# MCU.net
KiCad netlist of a schematic drawn in Altium Designer
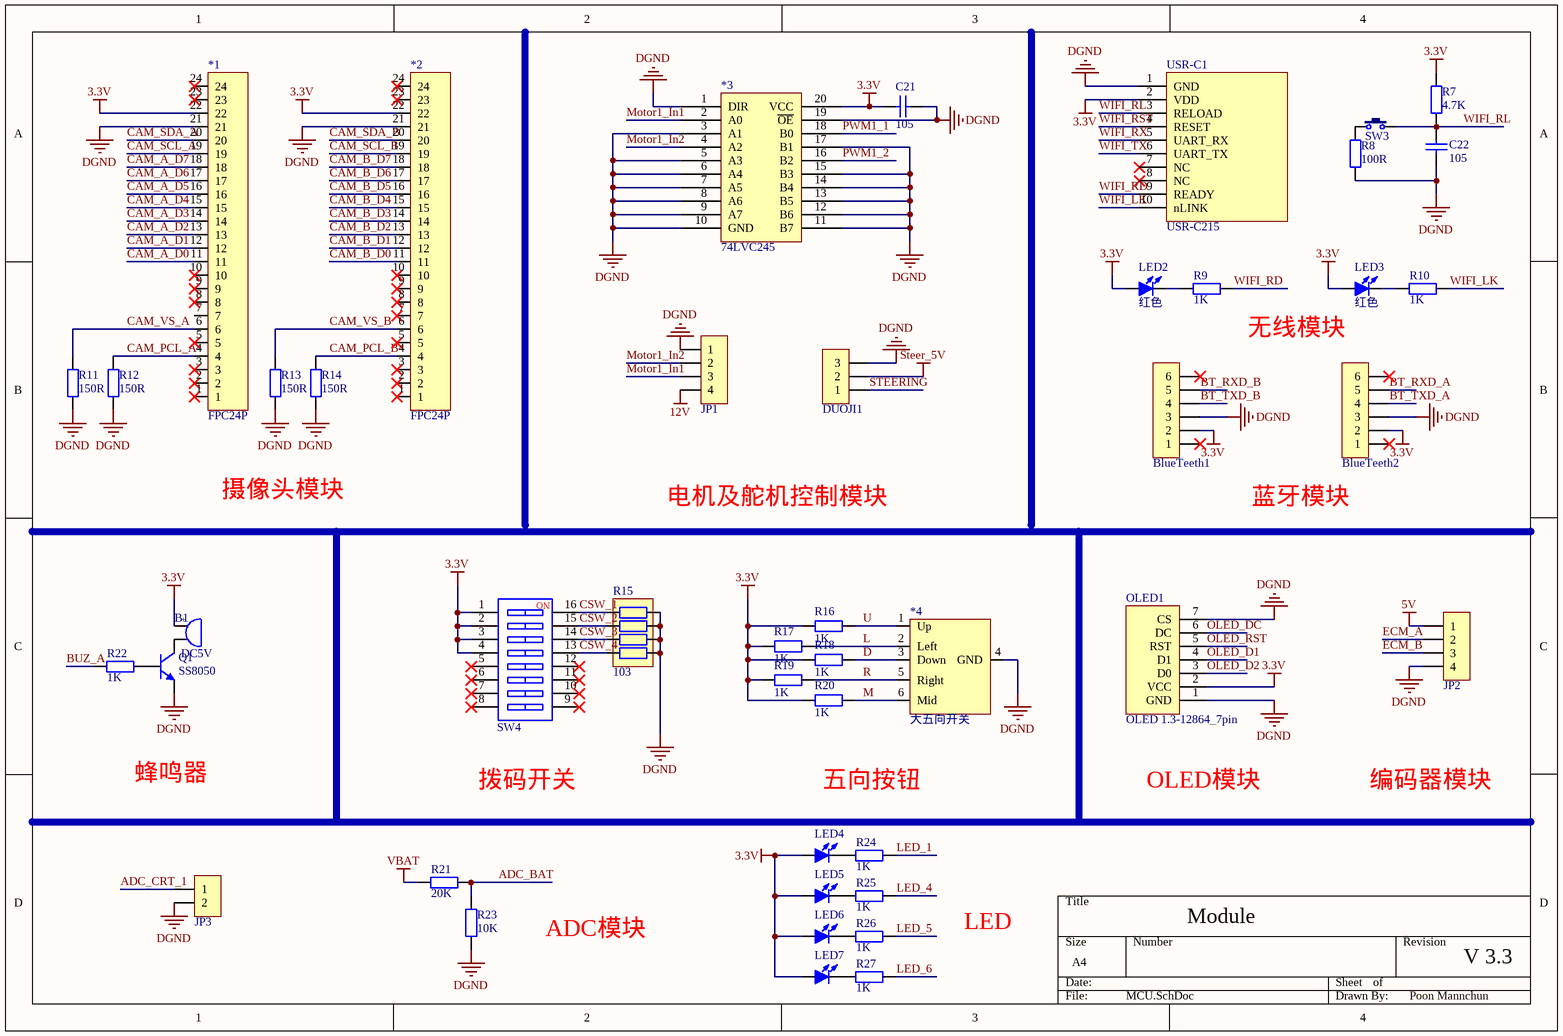
[diagram p0: MCU.SchDoc]

(export (version "E")
  (design (tool "Eeschema 10.0.6"))
  (components
    (comp (ref "*1")
      (value "FPC24P")
      (footprint "FH12-24S-0.5SV")
      (libsource (lib "LongMen") (part "FPC24P"))
    )
    (comp (ref "*2")
      (value "FPC24P")
      (footprint "FH12-24S-0.5SV")
      (libsource (lib "LongMen") (part "FPC24P"))
    )
    (comp (ref "*3") (value "74LVC245") (footprint "TSSOP-20") (libsource (lib "MIC5219") (part "74LVC245")))
    (comp (ref "*4") (value "大五向开关") (footprint "五向") (libsource (lib "5.1   - 按键-开关") (part "大五向开关")))
    (comp (ref "B1")
      (value "DC5V")
      (footprint "BEEP 5x9x5.5")
      (description "蜂鸣器")
      (fields (field (name "版权归属") "源创客"))
      (libsource (lib "未分类器件") (part "BEEP"))
    )
    (comp (ref "BlueTeeth1")
      (value "HDR-1X6")
      (footprint "HDR2.54-LI-6P")
      (description "6P接插件")
      (fields (field (name "版权归属") "源创客"))
      (libsource (lib "接插件") (part "Header 6"))
    )
    (comp (ref "BlueTeeth2")
      (value "HDR-1X6")
      (footprint "HDR2.54-LI-6P")
      (description "6P接插件")
      (fields (field (name "版权归属") "源创客"))
      (libsource (lib "接插件") (part "Header 6"))
    )
    (comp (ref "C21")
      (value "105")
      (footprint "C 0805_L")
      (description "Capacitor")
      (fields (field (name "PUBLISHER") "Altium Limited"))
      (libsource (lib "6-MK60DN512VLL10核心板") (part "CAP"))
    )
    (comp (ref "C22")
      (value "105")
      (footprint "C 0805_L")
      (description "Capacitor")
      (fields (field (name "PUBLISHER") "Altium Limited"))
      (libsource (lib "6-MK60DN512VLL10核心板") (part "CAP"))
    )
    (comp (ref "DUOJI1")
      (value "HDR-1X3")
      (footprint "HDR2.54-LI-3P")
      (description "3P接插件")
      (fields (field (name "版权归属") "源创客"))
      (libsource (lib "接插件") (part "Header 3"))
    )
    (comp (ref "JP1")
      (value "HDR-1X4")
      (footprint "HDR2.54-LI-4P")
      (description "4P接插件")
      (fields (field (name "版权归属") "源创客"))
      (libsource (lib "4.5   - 接插件-脚距2.54") (part "Header 4"))
    )
    (comp (ref "JP2")
      (value "HDR-1X4")
      (footprint "HDR2.54-LI-4P")
      (description "4P接插件")
      (fields (field (name "版权归属") "源创客"))
      (libsource (lib "4.5   - 接插件-脚距2.54") (part "Header 4"))
    )
    (comp (ref "JP3")
      (value "HDR-1X2")
      (footprint "HDR2.54-LI-2P")
      (description "2P接插件")
      (fields (field (name "版权归属") "源创客"))
      (libsource (lib "4.5   - 接插件-脚距2.54") (part "Header 2"))
    )
    (comp (ref "LED2")
      (value "红色")
      (footprint "LED 0805B")
      (description "贴片LED")
      (fields (field (name "版权归属") "源创客"))
      (libsource (lib "LED") (part "LED-SMD"))
    )
    (comp (ref "LED3")
      (value "红色")
      (footprint "LED 0805B")
      (description "贴片LED")
      (fields (field (name "版权归属") "源创客"))
      (libsource (lib "LED") (part "LED-SMD"))
    )
    (comp (ref "LED4")
      (value "红色")
      (footprint "LED 0805B")
      (description "贴片LED")
      (fields (field (name "版权归属") "源创客"))
      (libsource (lib "LED") (part "LED-SMD"))
    )
    (comp (ref "LED5")
      (value "红色")
      (footprint "LED 0805B")
      (description "贴片LED")
      (fields (field (name "版权归属") "源创客"))
      (libsource (lib "LED") (part "LED-SMD"))
    )
    (comp (ref "LED6")
      (value "红色")
      (footprint "LED 0805B")
      (description "贴片LED")
      (fields (field (name "版权归属") "源创客"))
      (libsource (lib "LED") (part "LED-SMD"))
    )
    (comp (ref "LED7")
      (value "红色")
      (footprint "LED 0805B")
      (description "贴片LED")
      (fields (field (name "版权归属") "源创客"))
      (libsource (lib "LED") (part "LED-SMD"))
    )
    (comp (ref "OLED1")
      (value "OLED 1.3-12864_7pin")
      (footprint "HDR2.54-M-LI-7P")
      (description "12864 点阵屏")
      (fields (field (name "版权归属") "源创客"))
      (libsource (lib "9.2   - 显示器件") (part "OLED 1.3-12864_7pin"))
    )
    (comp (ref "Q1")
      (value "SS8050")
      (footprint "SOT23-3L")
      (description "高频放大-NPN型")
      (fields (field (name "版权归属") "源创客"))
      (libsource (lib "三极管") (part "8050-SMD"))
    )
    (comp (ref "R7")
      (value "4.7K")
      (footprint "R 0805_L")
      (description "Resistor")
      (fields (field (name "PUBLISHER") "Altium Limited"))
      (libsource (lib "") (part "Res2_1"))
    )
    (comp (ref "R8")
      (value "100R")
      (footprint "R 0805_L")
      (description "Resistor")
      (fields (field (name "PUBLISHER") "Altium Limited"))
      (libsource (lib "") (part "Res2_1"))
    )
    (comp (ref "R9")
      (value "1K")
      (footprint "R 0805_L")
      (description "Resistor")
      (fields (field (name "PUBLISHER") "Altium Limited"))
      (libsource (lib "6-MK60DN512VLL10核心板") (part "Res2"))
    )
    (comp (ref "R10")
      (value "1K")
      (footprint "R 0805_L")
      (description "Resistor")
      (fields (field (name "PUBLISHER") "Altium Limited"))
      (libsource (lib "6-MK60DN512VLL10核心板") (part "Res2"))
    )
    (comp (ref "R11")
      (value "150R")
      (footprint "R 0805_L")
      (description "Resistor")
      (fields (field (name "PUBLISHER") "Altium Limited"))
      (libsource (lib "") (part "Res2_1"))
    )
    (comp (ref "R12")
      (value "150R")
      (footprint "R 0805_L")
      (description "Resistor")
      (fields (field (name "PUBLISHER") "Altium Limited"))
      (libsource (lib "") (part "Res2_1"))
    )
    (comp (ref "R13")
      (value "150R")
      (footprint "R 0805_L")
      (description "Resistor")
      (fields (field (name "PUBLISHER") "Altium Limited"))
      (libsource (lib "") (part "Res2_1"))
    )
    (comp (ref "R14")
      (value "150R")
      (footprint "R 0805_L")
      (description "Resistor")
      (fields (field (name "PUBLISHER") "Altium Limited"))
      (libsource (lib "") (part "Res2_1"))
    )
    (comp (ref "R15")
      (value "103")
      (footprint "RCA-8P4R-0603")
      (description "贴片网络排阻")
      (fields (field (name "版权归属") "源创客"))
      (libsource (lib "3.1   - 电阻-电容-电感") (part "R-8P4R"))
    )
    (comp (ref "R16")
      (value "1K")
      (footprint "R 0805_L")
      (description "贴片电阻")
      (fields (field (name "版权归属") "源创客"))
      (libsource (lib "3.1   - 电阻-电容-电感") (part "R"))
    )
    (comp (ref "R17")
      (value "1K")
      (footprint "R 0805_L")
      (description "贴片电阻")
      (fields (field (name "版权归属") "源创客"))
      (libsource (lib "3.1   - 电阻-电容-电感") (part "R"))
    )
    (comp (ref "R18")
      (value "1K")
      (footprint "R 0805_L")
      (description "贴片电阻")
      (fields (field (name "版权归属") "源创客"))
      (libsource (lib "3.1   - 电阻-电容-电感") (part "R"))
    )
    (comp (ref "R19")
      (value "1K")
      (footprint "R 0805_L")
      (description "贴片电阻")
      (fields (field (name "版权归属") "源创客"))
      (libsource (lib "3.1   - 电阻-电容-电感") (part "R"))
    )
    (comp (ref "R20")
      (value "1K")
      (footprint "R 0805_L")
      (description "贴片电阻")
      (fields (field (name "版权归属") "源创客"))
      (libsource (lib "3.1   - 电阻-电容-电感") (part "R"))
    )
    (comp (ref "R21")
      (value "20K")
      (footprint "R 0805_L")
      (description "Resistor")
      (fields (field (name "PUBLISHER") "Altium Limited"))
      (libsource (lib "6-MK60DN512VLL10核心板") (part "Res2"))
    )
    (comp (ref "R22")
      (value "1K")
      (footprint "R 0805_L")
      (description "Resistor")
      (fields (field (name "PUBLISHER") "Altium Limited"))
      (libsource (lib "6-MK60DN512VLL10核心板") (part "Res2"))
    )
    (comp (ref "R23")
      (value "10K")
      (footprint "R 0805_L")
      (description "Resistor")
      (fields (field (name "PUBLISHER") "Altium Limited"))
      (libsource (lib "") (part "Res2_1"))
    )
    (comp (ref "R24")
      (value "1K")
      (footprint "R 0805_L")
      (description "Resistor")
      (fields (field (name "PUBLISHER") "Altium Limited"))
      (libsource (lib "6-MK60DN512VLL10核心板") (part "Res2"))
    )
    (comp (ref "R25")
      (value "1K")
      (footprint "R 0805_L")
      (description "Resistor")
      (fields (field (name "PUBLISHER") "Altium Limited"))
      (libsource (lib "6-MK60DN512VLL10核心板") (part "Res2"))
    )
    (comp (ref "R26")
      (value "1K")
      (footprint "R 0805_L")
      (description "Resistor")
      (fields (field (name "PUBLISHER") "Altium Limited"))
      (libsource (lib "6-MK60DN512VLL10核心板") (part "Res2"))
    )
    (comp (ref "R27")
      (value "1K")
      (footprint "R 0805_L")
      (description "Resistor")
      (fields (field (name "PUBLISHER") "Altium Limited"))
      (libsource (lib "6-MK60DN512VLL10核心板") (part "Res2"))
    )
    (comp (ref "SW3")
      (value "3x6x5")
      (footprint "TSW SMD-3*6*2.5")
      (description "3x6轻触开关")
      (fields (field (name "版权归属") "源创客"))
      (libsource (lib "按键-开关") (part "TSW 3x6"))
    )
    (comp (ref "SW4")
      (value "CSW-8P")
      (footprint "CSW1.27 SMD-8P")
      (description "8路编码开关")
      (fields (field (name "版权归属") "源创客"))
      (libsource (lib "5.1   - 按键-开关") (part "CSW-8P"))
    )
    (comp (ref "USR-C1")
      (value "USR-C215")
      (footprint "DIP2.0*1-10-M")
      (fields (field (name "PUBLISHER") "*"))
      (libsource (lib "13.1 - 模块") (part "USR-C215"))
    )
  )
  (nets
    (net (code "1") (name "/ADC_BAT") (class "Default")
      (node (ref "R21") (pin "2") (pinfunction "2_2") (pintype "passive"))
      (node (ref "R23") (pin "2") (pinfunction "2_2") (pintype "passive"))
    )
    (net (code "2") (name "/ADC_CRT_1") (class "Default")
      (node (ref "JP3") (pin "1") (pinfunction "1_1") (pintype "passive"))
    )
    (net (code "3") (name "/BT_RXD_A") (class "Default")
      (node (ref "BlueTeeth2") (pin "5") (pinfunction "5_5") (pintype "passive"))
    )
    (net (code "4") (name "/BT_RXD_B") (class "Default")
      (node (ref "BlueTeeth1") (pin "5") (pinfunction "5_5") (pintype "passive"))
    )
    (net (code "5") (name "/BT_TXD_A") (class "Default")
      (node (ref "BlueTeeth2") (pin "4") (pinfunction "4_4") (pintype "passive"))
    )
    (net (code "6") (name "/BT_TXD_B") (class "Default")
      (node (ref "BlueTeeth1") (pin "4") (pinfunction "4_4") (pintype "passive"))
    )
    (net (code "7") (name "/BUZ_A") (class "Default")
      (node (ref "R22") (pin "1") (pinfunction "1_1") (pintype "passive"))
    )
    (net (code "8") (name "/CAM_A_D0") (class "Default")
      (node (ref "*1") (pin "11") (pinfunction "11_11") (pintype "passive"))
    )
    (net (code "9") (name "/CAM_A_D1") (class "Default")
      (node (ref "*1") (pin "12") (pinfunction "12_12") (pintype "passive"))
    )
    (net (code "10") (name "/CAM_A_D2") (class "Default")
      (node (ref "*1") (pin "13") (pinfunction "13_13") (pintype "passive"))
    )
    (net (code "11") (name "/CAM_A_D3") (class "Default")
      (node (ref "*1") (pin "14") (pinfunction "14_14") (pintype "passive"))
    )
    (net (code "12") (name "/CAM_A_D4") (class "Default")
      (node (ref "*1") (pin "15") (pinfunction "15_15") (pintype "passive"))
    )
    (net (code "13") (name "/CAM_A_D5") (class "Default")
      (node (ref "*1") (pin "16") (pinfunction "16_16") (pintype "passive"))
    )
    (net (code "14") (name "/CAM_A_D6") (class "Default")
      (node (ref "*1") (pin "17") (pinfunction "17_17") (pintype "passive"))
    )
    (net (code "15") (name "/CAM_A_D7") (class "Default")
      (node (ref "*1") (pin "18") (pinfunction "18_18") (pintype "passive"))
    )
    (net (code "16") (name "/CAM_B_D0") (class "Default")
      (node (ref "*2") (pin "11") (pinfunction "11_11") (pintype "passive"))
    )
    (net (code "17") (name "/CAM_B_D1") (class "Default")
      (node (ref "*2") (pin "12") (pinfunction "12_12") (pintype "passive"))
    )
    (net (code "18") (name "/CAM_B_D2") (class "Default")
      (node (ref "*2") (pin "13") (pinfunction "13_13") (pintype "passive"))
    )
    (net (code "19") (name "/CAM_B_D3") (class "Default")
      (node (ref "*2") (pin "14") (pinfunction "14_14") (pintype "passive"))
    )
    (net (code "20") (name "/CAM_B_D4") (class "Default")
      (node (ref "*2") (pin "15") (pinfunction "15_15") (pintype "passive"))
    )
    (net (code "21") (name "/CAM_B_D5") (class "Default")
      (node (ref "*2") (pin "16") (pinfunction "16_16") (pintype "passive"))
    )
    (net (code "22") (name "/CAM_B_D6") (class "Default")
      (node (ref "*2") (pin "17") (pinfunction "17_17") (pintype "passive"))
    )
    (net (code "23") (name "/CAM_B_D7") (class "Default")
      (node (ref "*2") (pin "18") (pinfunction "18_18") (pintype "passive"))
    )
    (net (code "24") (name "/CAM_PCL_A") (class "Default")
      (node (ref "*1") (pin "4") (pinfunction "4_4") (pintype "passive"))
      (node (ref "R12") (pin "2") (pinfunction "2_2") (pintype "passive"))
    )
    (net (code "25") (name "/CAM_PCL_B") (class "Default")
      (node (ref "*2") (pin "4") (pinfunction "4_4") (pintype "passive"))
      (node (ref "R14") (pin "2") (pinfunction "2_2") (pintype "passive"))
    )
    (net (code "26") (name "/CAM_SCL_A") (class "Default")
      (node (ref "*1") (pin "19") (pinfunction "19_19") (pintype "passive"))
    )
    (net (code "27") (name "/CAM_SCL_B") (class "Default")
      (node (ref "*2") (pin "19") (pinfunction "19_19") (pintype "passive"))
    )
    (net (code "28") (name "/CAM_SDA_A") (class "Default")
      (node (ref "*1") (pin "20") (pinfunction "20_20") (pintype "passive"))
    )
    (net (code "29") (name "/CAM_SDA_B") (class "Default")
      (node (ref "*2") (pin "20") (pinfunction "20_20") (pintype "passive"))
    )
    (net (code "30") (name "/CAM_VS_A") (class "Default")
      (node (ref "*1") (pin "6") (pinfunction "6_6") (pintype "passive"))
      (node (ref "R11") (pin "2") (pinfunction "2_2") (pintype "passive"))
    )
    (net (code "31") (name "/CAM_VS_B") (class "Default")
      (node (ref "*2") (pin "6") (pinfunction "6_6") (pintype "passive"))
      (node (ref "R13") (pin "2") (pinfunction "2_2") (pintype "passive"))
    )
    (net (code "32") (name "/CSW_1") (class "Default")
      (node (ref "R15") (pin "1") (pinfunction "1_1") (pintype "passive"))
      (node (ref "SW4") (pin "16") (pinfunction "16_16") (pintype "passive"))
    )
    (net (code "33") (name "/CSW_2") (class "Default")
      (node (ref "R15") (pin "2") (pinfunction "2_2") (pintype "passive"))
      (node (ref "SW4") (pin "15") (pinfunction "15_15") (pintype "passive"))
    )
    (net (code "34") (name "/CSW_3") (class "Default")
      (node (ref "R15") (pin "3") (pinfunction "3_3") (pintype "passive"))
      (node (ref "SW4") (pin "14") (pinfunction "14_14") (pintype "passive"))
    )
    (net (code "35") (name "/CSW_4") (class "Default")
      (node (ref "R15") (pin "4") (pinfunction "4_4") (pintype "passive"))
      (node (ref "SW4") (pin "13") (pinfunction "13_13") (pintype "passive"))
    )
    (net (code "36") (name "/D") (class "Default")
      (node (ref "*4") (pin "3") (pinfunction "Down_3") (pintype "passive"))
      (node (ref "R18") (pin "2") (pinfunction "2_2") (pintype "passive"))
    )
    (net (code "37") (name "/ECM_A") (class "Default")
      (node (ref "JP2") (pin "2") (pinfunction "2_2") (pintype "passive"))
    )
    (net (code "38") (name "/ECM_B") (class "Default")
      (node (ref "JP2") (pin "3") (pinfunction "3_3") (pintype "passive"))
    )
    (net (code "39") (name "/L") (class "Default")
      (node (ref "*4") (pin "2") (pinfunction "Left_2") (pintype "passive"))
      (node (ref "R17") (pin "2") (pinfunction "2_2") (pintype "passive"))
    )
    (net (code "40") (name "/LED_1") (class "Default")
      (node (ref "R24") (pin "2") (pinfunction "2_2") (pintype "passive"))
    )
    (net (code "41") (name "/LED_4") (class "Default")
      (node (ref "R25") (pin "2") (pinfunction "2_2") (pintype "passive"))
    )
    (net (code "42") (name "/LED_5") (class "Default")
      (node (ref "R26") (pin "2") (pinfunction "2_2") (pintype "passive"))
    )
    (net (code "43") (name "/LED_6") (class "Default")
      (node (ref "R27") (pin "2") (pinfunction "2_2") (pintype "passive"))
    )
    (net (code "44") (name "/M") (class "Default")
      (node (ref "*4") (pin "6") (pinfunction "Mid_6") (pintype "passive"))
      (node (ref "R20") (pin "2") (pinfunction "2_2") (pintype "passive"))
    )
    (net (code "45") (name "/Motor1_In1") (class "Default")
      (node (ref "*3") (pin "2") (pinfunction "A0_2") (pintype "passive"))
      (node (ref "JP1") (pin "3") (pinfunction "3_3") (pintype "passive"))
    )
    (net (code "46") (name "/Motor1_In2") (class "Default")
      (node (ref "*3") (pin "4") (pinfunction "A2_4") (pintype "passive"))
      (node (ref "JP1") (pin "2") (pinfunction "2_2") (pintype "passive"))
    )
    (net (code "47") (name "/OLED_D1") (class "Default")
      (node (ref "OLED1") (pin "4") (pinfunction "D1_4") (pintype "passive"))
    )
    (net (code "48") (name "/OLED_D2") (class "Default")
      (node (ref "OLED1") (pin "3") (pinfunction "D0_3") (pintype "passive"))
    )
    (net (code "49") (name "/OLED_DC") (class "Default")
      (node (ref "OLED1") (pin "6") (pinfunction "DC_6") (pintype "passive"))
    )
    (net (code "50") (name "/OLED_RST") (class "Default")
      (node (ref "OLED1") (pin "5") (pinfunction "RST_5") (pintype "passive"))
    )
    (net (code "51") (name "/PWM1_1") (class "Default")
      (node (ref "*3") (pin "18") (pinfunction "B0_18") (pintype "passive"))
    )
    (net (code "52") (name "/PWM1_2") (class "Default")
      (node (ref "*3") (pin "16") (pinfunction "B2_16") (pintype "passive"))
    )
    (net (code "53") (name "/R") (class "Default")
      (node (ref "*4") (pin "5") (pinfunction "Right_5") (pintype "passive"))
      (node (ref "R19") (pin "2") (pinfunction "2_2") (pintype "passive"))
    )
    (net (code "54") (name "/STEERING") (class "Default")
      (node (ref "DUOJI1") (pin "1") (pinfunction "1_1") (pintype "passive"))
    )
    (net (code "55") (name "/U") (class "Default")
      (node (ref "*4") (pin "1") (pinfunction "Up_1") (pintype "passive"))
      (node (ref "R16") (pin "2") (pinfunction "2_2") (pintype "passive"))
    )
    (net (code "56") (name "/WIFI_LK") (class "Default")
      (node (ref "R10") (pin "2") (pinfunction "2_2") (pintype "passive"))
      (node (ref "USR-C1") (pin "10") (pinfunction "nLINK_10") (pintype "passive"))
    )
    (net (code "57") (name "/WIFI_RD") (class "Default")
      (node (ref "R9") (pin "2") (pinfunction "2_2") (pintype "passive"))
      (node (ref "USR-C1") (pin "9") (pinfunction "READY_9") (pintype "passive"))
    )
    (net (code "58") (name "/WIFI_RL") (class "Default")
      (node (ref "C22") (pin "2") (pinfunction "2_2") (pintype "passive"))
      (node (ref "R7") (pin "1") (pinfunction "1_1") (pintype "passive"))
      (node (ref "SW3") (pin "2") (pinfunction "2_2") (pintype "passive"))
      (node (ref "USR-C1") (pin "3") (pinfunction "RELOAD_3") (pintype "passive"))
    )
    (net (code "59") (name "/WIFI_RST") (class "Default")
      (node (ref "USR-C1") (pin "4") (pinfunction "RESET_4") (pintype "passive"))
    )
    (net (code "60") (name "/WIFI_RX") (class "Default")
      (node (ref "USR-C1") (pin "5") (pinfunction "UART_RX_5") (pintype "passive"))
    )
    (net (code "61") (name "/WIFI_TX") (class "Default")
      (node (ref "USR-C1") (pin "6") (pinfunction "UART_TX_6") (pintype "passive"))
    )
    (net (code "62") (name "3.3V") (class "Default")
      (node (ref "*1") (pin "22") (pinfunction "22_22") (pintype "passive"))
      (node (ref "*2") (pin "22") (pinfunction "22_22") (pintype "passive"))
      (node (ref "*3") (pin "20") (pinfunction "VCC_20") (pintype "passive"))
      (node (ref "B1") (pin "1") (pinfunction "1_1") (pintype "passive"))
      (node (ref "BlueTeeth1") (pin "2") (pinfunction "2_2") (pintype "passive"))
      (node (ref "BlueTeeth2") (pin "2") (pinfunction "2_2") (pintype "passive"))
      (node (ref "C21") (pin "2") (pinfunction "2_2") (pintype "passive"))
      (node (ref "LED2") (pin "1") (pinfunction "A_1") (pintype "passive"))
      (node (ref "LED3") (pin "1") (pinfunction "A_1") (pintype "passive"))
      (node (ref "LED4") (pin "1") (pinfunction "A_1") (pintype "passive"))
      (node (ref "LED5") (pin "1") (pinfunction "A_1") (pintype "passive"))
      (node (ref "LED6") (pin "1") (pinfunction "A_1") (pintype "passive"))
      (node (ref "LED7") (pin "1") (pinfunction "A_1") (pintype "passive"))
      (node (ref "OLED1") (pin "2") (pinfunction "VCC_2") (pintype "passive"))
      (node (ref "R16") (pin "1") (pinfunction "1_1") (pintype "passive"))
      (node (ref "R17") (pin "1") (pinfunction "1_1") (pintype "passive"))
      (node (ref "R18") (pin "1") (pinfunction "1_1") (pintype "passive"))
      (node (ref "R19") (pin "1") (pinfunction "1_1") (pintype "passive"))
      (node (ref "R20") (pin "1") (pinfunction "1_1") (pintype "passive"))
      (node (ref "R7") (pin "2") (pinfunction "2_2") (pintype "passive"))
      (node (ref "SW4") (pin "1") (pinfunction "1_1") (pintype "passive"))
      (node (ref "SW4") (pin "2") (pinfunction "2_2") (pintype "passive"))
      (node (ref "SW4") (pin "3") (pinfunction "3_3") (pintype "passive"))
      (node (ref "SW4") (pin "4") (pinfunction "4_4") (pintype "passive"))
      (node (ref "USR-C1") (pin "2") (pinfunction "VDD_2") (pintype "passive"))
    )
    (net (code "63") (name "5V") (class "Default")
      (node (ref "JP2") (pin "1") (pinfunction "1_1") (pintype "passive"))
    )
    (net (code "64") (name "12V") (class "Default")
      (node (ref "JP1") (pin "4") (pinfunction "4_4") (pintype "passive"))
    )
    (net (code "65") (name "DGND") (class "Default")
      (node (ref "*1") (pin "21") (pinfunction "21_21") (pintype "passive"))
      (node (ref "*2") (pin "21") (pinfunction "21_21") (pintype "passive"))
      (node (ref "*3") (pin "1") (pinfunction "DIR_1") (pintype "passive"))
      (node (ref "*3") (pin "10") (pinfunction "GND_10") (pintype "passive"))
      (node (ref "*3") (pin "11") (pinfunction "B7_11") (pintype "passive"))
      (node (ref "*3") (pin "12") (pinfunction "B6_12") (pintype "passive"))
      (node (ref "*3") (pin "13") (pinfunction "B5_13") (pintype "passive"))
      (node (ref "*3") (pin "14") (pinfunction "B4_14") (pintype "passive"))
      (node (ref "*3") (pin "15") (pinfunction "B3_15") (pintype "passive"))
      (node (ref "*3") (pin "17") (pinfunction "B1_17") (pintype "passive"))
      (node (ref "*3") (pin "19") (pinfunction "~{OE}_19") (pintype "passive"))
      (node (ref "*3") (pin "3") (pinfunction "A1_3") (pintype "passive"))
      (node (ref "*3") (pin "5") (pinfunction "A3_5") (pintype "passive"))
      (node (ref "*3") (pin "6") (pinfunction "A4_6") (pintype "passive"))
      (node (ref "*3") (pin "7") (pinfunction "A5_7") (pintype "passive"))
      (node (ref "*3") (pin "8") (pinfunction "A6_8") (pintype "passive"))
      (node (ref "*3") (pin "9") (pinfunction "A7_9") (pintype "passive"))
      (node (ref "*4") (pin "4") (pinfunction "GND_4") (pintype "passive"))
      (node (ref "BlueTeeth1") (pin "3") (pinfunction "3_3") (pintype "passive"))
      (node (ref "BlueTeeth2") (pin "3") (pinfunction "3_3") (pintype "passive"))
      (node (ref "C21") (pin "1") (pinfunction "1_1") (pintype "passive"))
      (node (ref "C22") (pin "1") (pinfunction "1_1") (pintype "passive"))
      (node (ref "DUOJI1") (pin "3") (pinfunction "3_3") (pintype "passive"))
      (node (ref "JP1") (pin "1") (pinfunction "1_1") (pintype "passive"))
      (node (ref "JP2") (pin "4") (pinfunction "4_4") (pintype "passive"))
      (node (ref "JP3") (pin "2") (pinfunction "2_2") (pintype "passive"))
      (node (ref "OLED1") (pin "1") (pinfunction "GND_1") (pintype "passive"))
      (node (ref "OLED1") (pin "7") (pinfunction "CS_7") (pintype "passive"))
      (node (ref "Q1") (pin "2") (pinfunction "E_2") (pintype "passive"))
      (node (ref "R11") (pin "1") (pinfunction "1_1") (pintype "passive"))
      (node (ref "R12") (pin "1") (pinfunction "1_1") (pintype "passive"))
      (node (ref "R13") (pin "1") (pinfunction "1_1") (pintype "passive"))
      (node (ref "R14") (pin "1") (pinfunction "1_1") (pintype "passive"))
      (node (ref "R15") (pin "5") (pinfunction "5_5") (pintype "passive"))
      (node (ref "R15") (pin "6") (pinfunction "6_6") (pintype "passive"))
      (node (ref "R15") (pin "7") (pinfunction "7_7") (pintype "passive"))
      (node (ref "R15") (pin "8") (pinfunction "8_8") (pintype "passive"))
      (node (ref "R23") (pin "1") (pinfunction "1_1") (pintype "passive"))
      (node (ref "R8") (pin "1") (pinfunction "1_1") (pintype "passive"))
      (node (ref "USR-C1") (pin "1") (pinfunction "GND_1") (pintype "passive"))
    )
    (net (code "66") (name "Net-(LED2-K)") (class "Default")
      (node (ref "LED2") (pin "2") (pinfunction "K_2") (pintype "passive"))
      (node (ref "R9") (pin "1") (pinfunction "1_1") (pintype "passive"))
    )
    (net (code "67") (name "Net-(LED3-K)") (class "Default")
      (node (ref "LED3") (pin "2") (pinfunction "K_2") (pintype "passive"))
      (node (ref "R10") (pin "1") (pinfunction "1_1") (pintype "passive"))
    )
    (net (code "68") (name "Net-(LED4-K)") (class "Default")
      (node (ref "LED4") (pin "2") (pinfunction "K_2") (pintype "passive"))
      (node (ref "R24") (pin "1") (pinfunction "1_1") (pintype "passive"))
    )
    (net (code "69") (name "Net-(LED5-K)") (class "Default")
      (node (ref "LED5") (pin "2") (pinfunction "K_2") (pintype "passive"))
      (node (ref "R25") (pin "1") (pinfunction "1_1") (pintype "passive"))
    )
    (net (code "70") (name "Net-(LED6-K)") (class "Default")
      (node (ref "LED6") (pin "2") (pinfunction "K_2") (pintype "passive"))
      (node (ref "R26") (pin "1") (pinfunction "1_1") (pintype "passive"))
    )
    (net (code "71") (name "Net-(LED7-K)") (class "Default")
      (node (ref "LED7") (pin "2") (pinfunction "K_2") (pintype "passive"))
      (node (ref "R27") (pin "1") (pinfunction "1_1") (pintype "passive"))
    )
    (net (code "72") (name "Net-(Q1-B)") (class "Default")
      (node (ref "Q1") (pin "1") (pinfunction "B_1") (pintype "passive"))
      (node (ref "R22") (pin "2") (pinfunction "2_2") (pintype "passive"))
    )
    (net (code "73") (name "Net-(Q1-C)") (class "Default")
      (node (ref "B1") (pin "2") (pinfunction "2_2") (pintype "passive"))
      (node (ref "Q1") (pin "3") (pinfunction "C_3") (pintype "passive"))
    )
    (net (code "74") (name "Net-(R8-Pad2)") (class "Default")
      (node (ref "R8") (pin "2") (pinfunction "2_2") (pintype "passive"))
      (node (ref "SW3") (pin "1") (pinfunction "1_1") (pintype "passive"))
    )
    (net (code "75") (name "Steer_5V") (class "Default")
      (node (ref "DUOJI1") (pin "2") (pinfunction "2_2") (pintype "passive"))
    )
    (net (code "76") (name "VBAT") (class "Default")
      (node (ref "R21") (pin "1") (pinfunction "1_1") (pintype "passive"))
    )
    (net (code "77") (name "unconnected-(*1-Pad1)") (class "Default")
      (node (ref "*1") (pin "1") (pinfunction "1_1") (pintype "passive+no_connect"))
    )
    (net (code "78") (name "unconnected-(*1-Pad2)") (class "Default")
      (node (ref "*1") (pin "2") (pinfunction "2_2") (pintype "passive+no_connect"))
    )
    (net (code "79") (name "unconnected-(*1-Pad3)") (class "Default")
      (node (ref "*1") (pin "3") (pinfunction "3_3") (pintype "passive+no_connect"))
    )
    (net (code "80") (name "unconnected-(*1-Pad5)") (class "Default")
      (node (ref "*1") (pin "5") (pinfunction "5_5") (pintype "passive+no_connect"))
    )
    (net (code "81") (name "unconnected-(*1-Pad7)") (class "Default")
      (node (ref "*1") (pin "7") (pinfunction "7_7") (pintype "passive"))
    )
    (net (code "82") (name "unconnected-(*1-Pad8)") (class "Default")
      (node (ref "*1") (pin "8") (pinfunction "8_8") (pintype "passive+no_connect"))
    )
    (net (code "83") (name "unconnected-(*1-Pad9)") (class "Default")
      (node (ref "*1") (pin "9") (pinfunction "9_9") (pintype "passive+no_connect"))
    )
    (net (code "84") (name "unconnected-(*1-Pad10)") (class "Default")
      (node (ref "*1") (pin "10") (pinfunction "10_10") (pintype "passive+no_connect"))
    )
    (net (code "85") (name "unconnected-(*1-Pad23)") (class "Default")
      (node (ref "*1") (pin "23") (pinfunction "23_23") (pintype "passive+no_connect"))
    )
    (net (code "86") (name "unconnected-(*1-Pad24)") (class "Default")
      (node (ref "*1") (pin "24") (pinfunction "24_24") (pintype "passive+no_connect"))
    )
    (net (code "87") (name "unconnected-(*2-Pad1)") (class "Default")
      (node (ref "*2") (pin "1") (pinfunction "1_1") (pintype "passive+no_connect"))
    )
    (net (code "88") (name "unconnected-(*2-Pad2)") (class "Default")
      (node (ref "*2") (pin "2") (pinfunction "2_2") (pintype "passive+no_connect"))
    )
    (net (code "89") (name "unconnected-(*2-Pad3)") (class "Default")
      (node (ref "*2") (pin "3") (pinfunction "3_3") (pintype "passive+no_connect"))
    )
    (net (code "90") (name "unconnected-(*2-Pad5)") (class "Default")
      (node (ref "*2") (pin "5") (pinfunction "5_5") (pintype "passive+no_connect"))
    )
    (net (code "91") (name "unconnected-(*2-Pad7)") (class "Default")
      (node (ref "*2") (pin "7") (pinfunction "7_7") (pintype "passive+no_connect"))
    )
    (net (code "92") (name "unconnected-(*2-Pad8)") (class "Default")
      (node (ref "*2") (pin "8") (pinfunction "8_8") (pintype "passive+no_connect"))
    )
    (net (code "93") (name "unconnected-(*2-Pad9)") (class "Default")
      (node (ref "*2") (pin "9") (pinfunction "9_9") (pintype "passive+no_connect"))
    )
    (net (code "94") (name "unconnected-(*2-Pad10)") (class "Default")
      (node (ref "*2") (pin "10") (pinfunction "10_10") (pintype "passive+no_connect"))
    )
    (net (code "95") (name "unconnected-(*2-Pad23)") (class "Default")
      (node (ref "*2") (pin "23") (pinfunction "23_23") (pintype "passive+no_connect"))
    )
    (net (code "96") (name "unconnected-(*2-Pad24)") (class "Default")
      (node (ref "*2") (pin "24") (pinfunction "24_24") (pintype "passive+no_connect"))
    )
    (net (code "97") (name "unconnected-(BlueTeeth1-Pad1)") (class "Default")
      (node (ref "BlueTeeth1") (pin "1") (pinfunction "1_1") (pintype "passive+no_connect"))
    )
    (net (code "98") (name "unconnected-(BlueTeeth1-Pad6)") (class "Default")
      (node (ref "BlueTeeth1") (pin "6") (pinfunction "6_6") (pintype "passive+no_connect"))
    )
    (net (code "99") (name "unconnected-(BlueTeeth2-Pad1)") (class "Default")
      (node (ref "BlueTeeth2") (pin "1") (pinfunction "1_1") (pintype "passive+no_connect"))
    )
    (net (code "100") (name "unconnected-(BlueTeeth2-Pad6)") (class "Default")
      (node (ref "BlueTeeth2") (pin "6") (pinfunction "6_6") (pintype "passive+no_connect"))
    )
    (net (code "101") (name "unconnected-(SW4-Pad5)") (class "Default")
      (node (ref "SW4") (pin "5") (pinfunction "5_5") (pintype "passive+no_connect"))
    )
    (net (code "102") (name "unconnected-(SW4-Pad6)") (class "Default")
      (node (ref "SW4") (pin "6") (pinfunction "6_6") (pintype "passive+no_connect"))
    )
    (net (code "103") (name "unconnected-(SW4-Pad7)") (class "Default")
      (node (ref "SW4") (pin "7") (pinfunction "7_7") (pintype "passive+no_connect"))
    )
    (net (code "104") (name "unconnected-(SW4-Pad8)") (class "Default")
      (node (ref "SW4") (pin "8") (pinfunction "8_8") (pintype "passive+no_connect"))
    )
    (net (code "105") (name "unconnected-(SW4-Pad9)") (class "Default")
      (node (ref "SW4") (pin "9") (pinfunction "9_9") (pintype "passive+no_connect"))
    )
    (net (code "106") (name "unconnected-(SW4-Pad10)") (class "Default")
      (node (ref "SW4") (pin "10") (pinfunction "10_10") (pintype "passive+no_connect"))
    )
    (net (code "107") (name "unconnected-(SW4-Pad11)") (class "Default")
      (node (ref "SW4") (pin "11") (pinfunction "11_11") (pintype "passive+no_connect"))
    )
    (net (code "108") (name "unconnected-(SW4-Pad12)") (class "Default")
      (node (ref "SW4") (pin "12") (pinfunction "12_12") (pintype "passive+no_connect"))
    )
    (net (code "109") (name "unconnected-(USR-C1-NC-Pad7)") (class "Default")
      (node (ref "USR-C1") (pin "7") (pinfunction "NC_7") (pintype "passive+no_connect"))
    )
    (net (code "110") (name "unconnected-(USR-C1-NC-Pad8)") (class "Default")
      (node (ref "USR-C1") (pin "8") (pinfunction "NC_8") (pintype "passive+no_connect"))
    )
  )
)
